# RcCarMainBoard.net
KiCad netlist of a schematic drawn in EAGLE
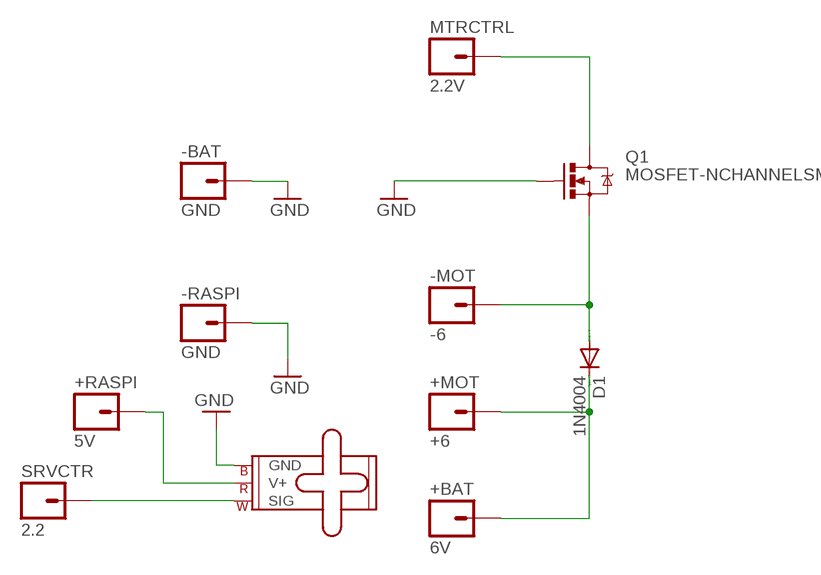
[diagram p0: schematic, sheet 1]

(export (version "E")
  (design (tool "Eeschema 10.0.6"))
  (components
    (comp (ref "+BAT")
      (value "6V")
      (footprint "eagle-import:1X01")
      (libsource (lib "eagle-import") (part "M01PTH"))
    )
    (comp (ref "+MOT")
      (value "+6")
      (footprint "eagle-import:1X01")
      (libsource (lib "eagle-import") (part "M01PTH"))
    )
    (comp (ref "+RASPI")
      (value "5V")
      (footprint "eagle-import:1X01")
      (libsource (lib "eagle-import") (part "M01PTH"))
    )
    (comp (ref "-BAT")
      (value "GND")
      (footprint "eagle-import:1X01")
      (libsource (lib "eagle-import") (part "M01PTH"))
    )
    (comp (ref "-MOT")
      (value "-6")
      (footprint "eagle-import:1X01")
      (libsource (lib "eagle-import") (part "M01PTH"))
    )
    (comp (ref "-RASPI")
      (value "GND")
      (footprint "eagle-import:1X01")
      (libsource (lib "eagle-import") (part "M01PTH"))
    )
    (comp (ref "D1")
      (value "1N4004")
      (footprint "eagle-import:DO41-10")
      (libsource (lib "eagle-import") (part "1N4004"))
    )
    (comp (ref "M1")
      (value "SMALL_SERVO")
      (footprint "eagle-import:1X03")
      (libsource (lib "eagle-import") (part "SMALL_SERVO"))
    )
    (comp (ref "MTRCTRL")
      (value "2.2V")
      (footprint "eagle-import:1X01")
      (libsource (lib "eagle-import") (part "M01PTH"))
    )
    (comp (ref "Q1")
      (value "MOSFET-NCHANNELSMD")
      (footprint "eagle-import:SOT23-3")
      (libsource (lib "eagle-import") (part "MOSFET-NCHANNELSMD"))
    )
    (comp (ref "SRVCTR")
      (value "2.2")
      (footprint "eagle-import:1X01")
      (libsource (lib "eagle-import") (part "M01PTH"))
    )
  )
  (nets
    (net (code "1") (name "GND") (class "Default")
      (node (ref "-BAT") (pin "1") (pinfunction "1_1") (pintype "passive"))
      (node (ref "-RASPI") (pin "1") (pinfunction "1_1") (pintype "passive"))
      (node (ref "M1") (pin "3") (pinfunction "GND_3") (pintype "bidirectional"))
      (node (ref "Q1") (pin "1") (pinfunction "G_1") (pintype "passive"))
    )
    (net (code "2") (name "Net-(+BAT-Pad1)") (class "Default")
      (node (ref "+BAT") (pin "1") (pinfunction "1_1") (pintype "passive"))
      (node (ref "+MOT") (pin "1") (pinfunction "1_1") (pintype "passive"))
      (node (ref "D1") (pin "C") (pinfunction "C_C") (pintype "passive"))
    )
    (net (code "3") (name "Net-(M1-SIG)") (class "Default")
      (node (ref "M1") (pin "1") (pinfunction "SIG_1") (pintype "bidirectional"))
      (node (ref "SRVCTR") (pin "1") (pinfunction "1_1") (pintype "passive"))
    )
    (net (code "4") (name "Net-(M1-V+)") (class "Default")
      (node (ref "+RASPI") (pin "1") (pinfunction "1_1") (pintype "passive"))
      (node (ref "M1") (pin "2") (pinfunction "V+_2") (pintype "bidirectional"))
    )
    (net (code "5") (name "Net-(Q1-D)") (class "Default")
      (node (ref "MTRCTRL") (pin "1") (pinfunction "1_1") (pintype "passive"))
      (node (ref "Q1") (pin "3") (pinfunction "D_3") (pintype "passive"))
    )
    (net (code "6") (name "Net-(Q1-S)") (class "Default")
      (node (ref "-MOT") (pin "1") (pinfunction "1_1") (pintype "passive"))
      (node (ref "D1") (pin "A") (pinfunction "A_A") (pintype "passive"))
      (node (ref "Q1") (pin "2") (pinfunction "S_2") (pintype "passive"))
    )
  )
)
